# SCH_uCompute_NRF24L01_module_2026-04-06.net
KiCad netlist of a schematic drawn in EasyEDA
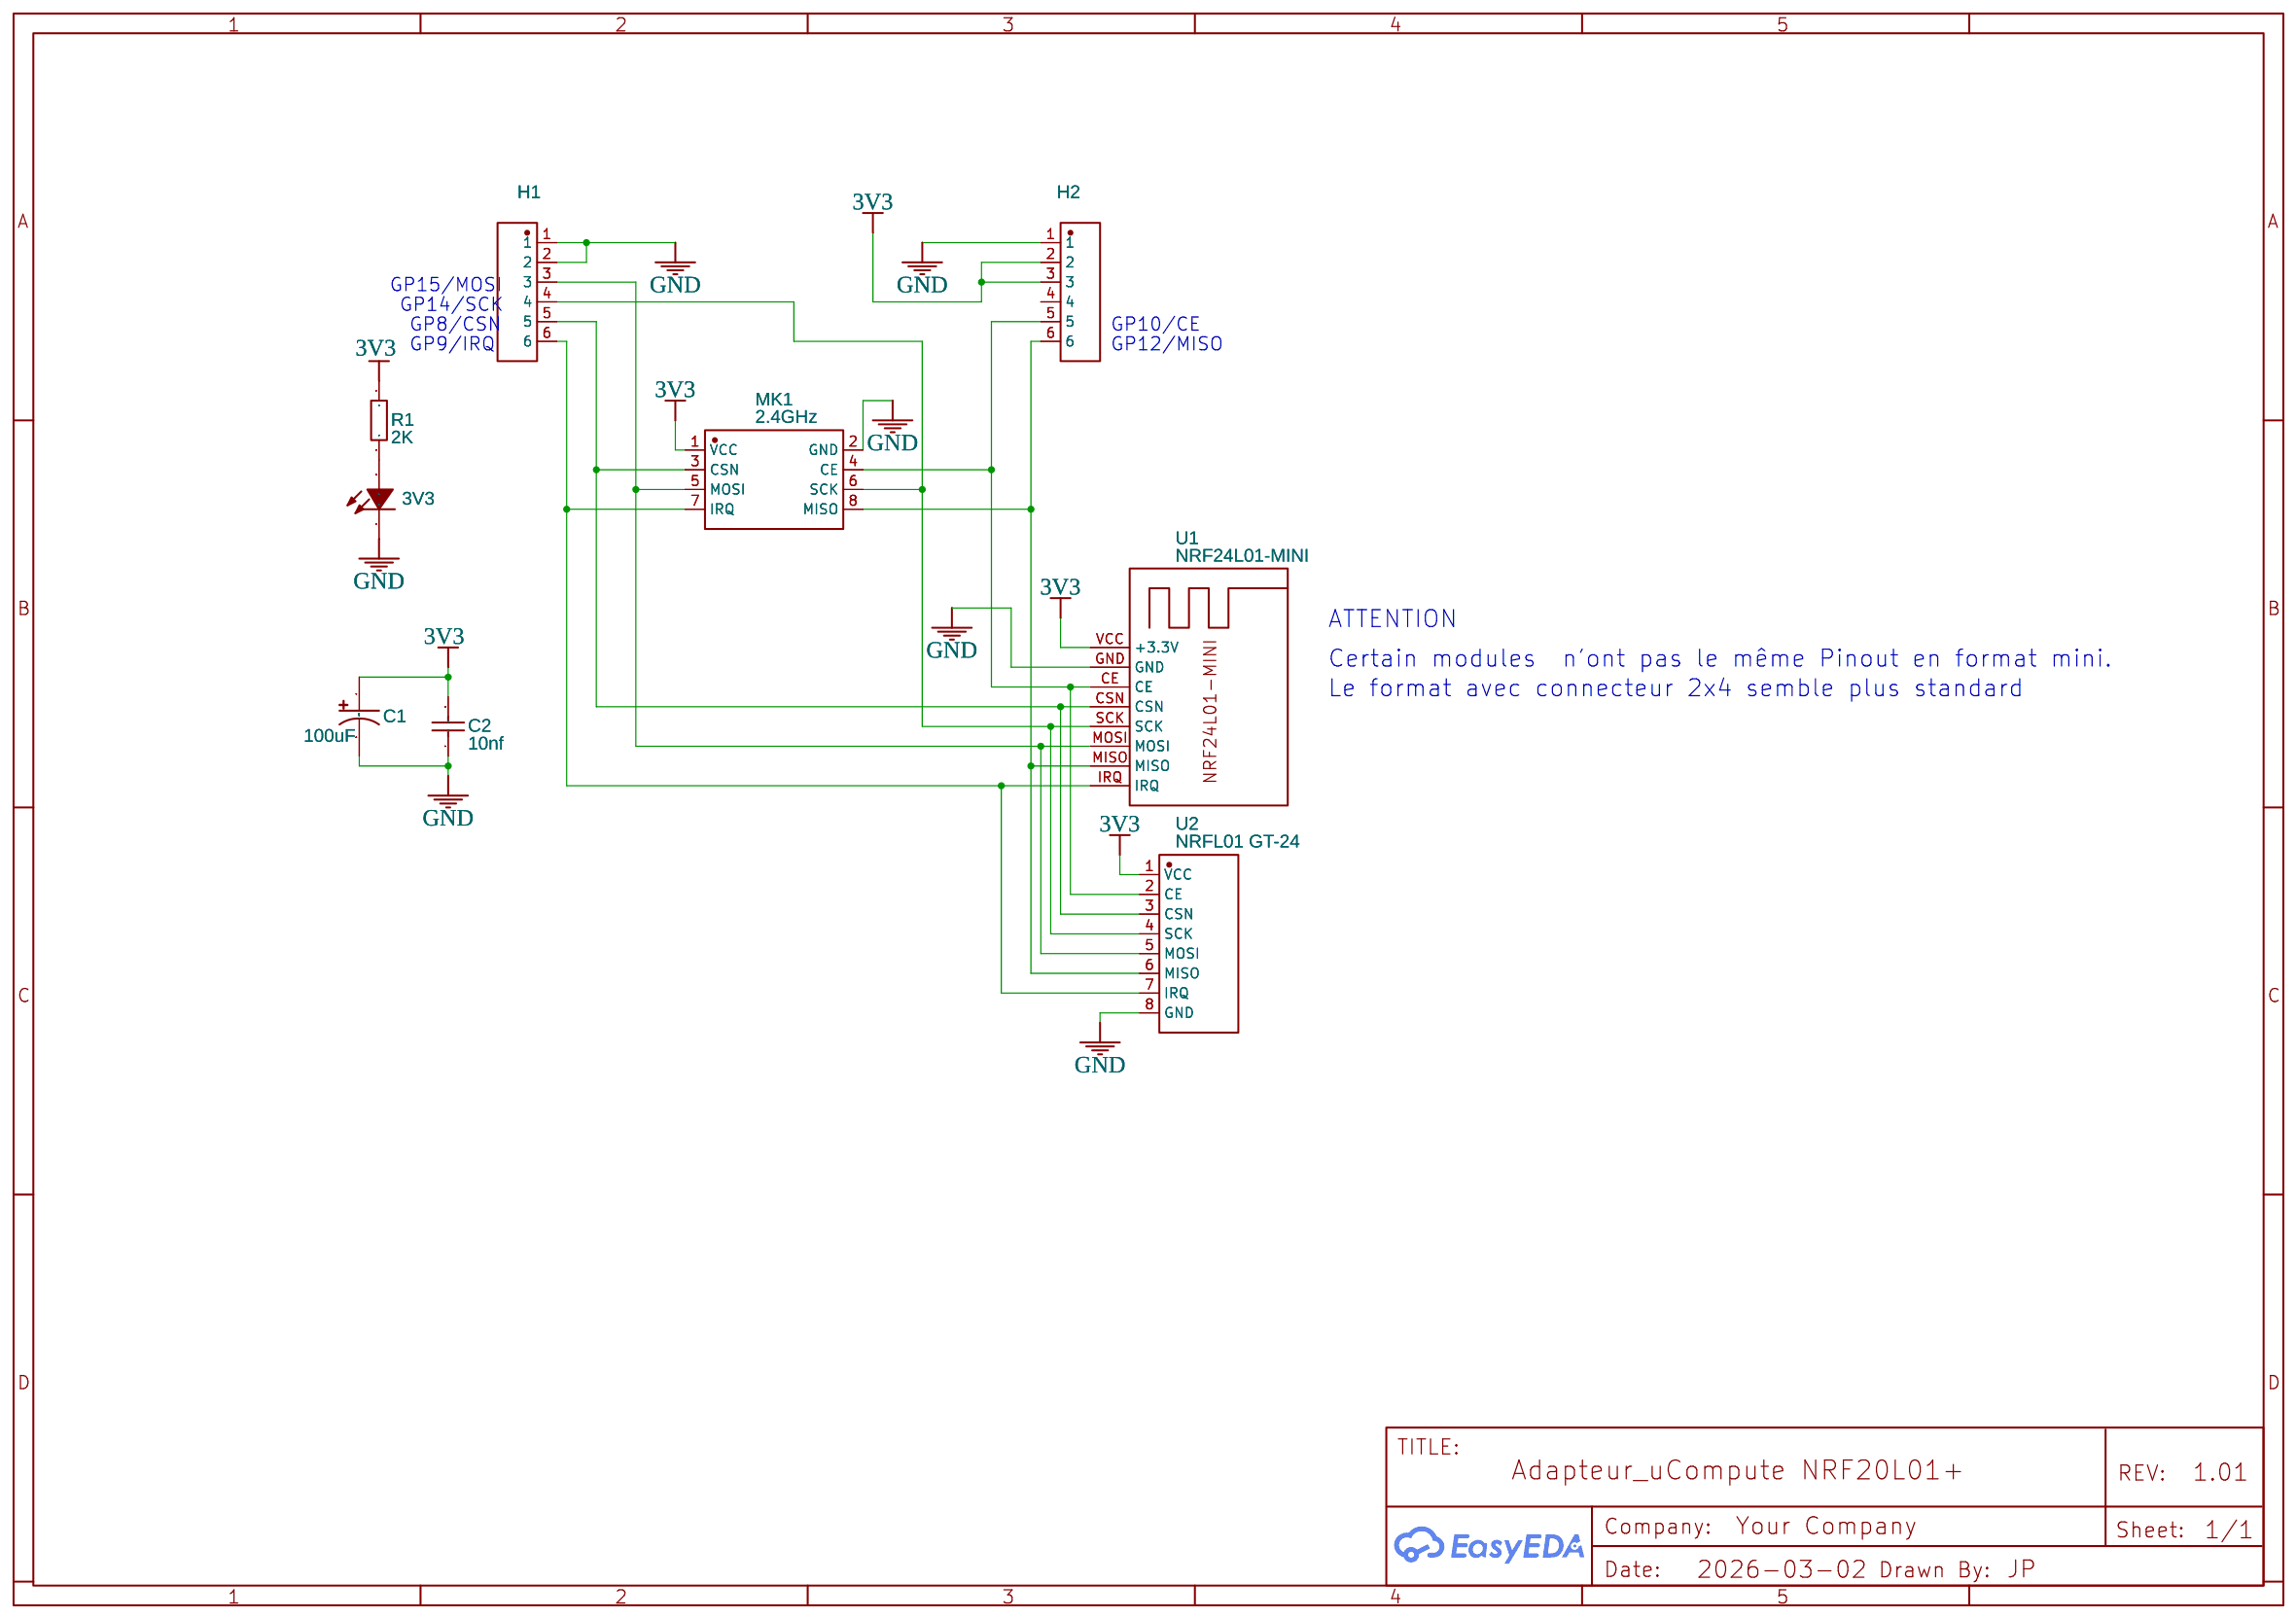
[diagram p0: schematic sheet]

(export (version "E")
  (design (tool "Eeschema 10.0.6"))
  (components
    (comp (ref "3V3")
      (value "XL-1206QPC")
      (fields (field (name "Manufacturer") "LCSC"))
      (libsource (lib "") (part "XL-1206QPC"))
    )
    (comp (ref "C1")
      (value "100uF")
      (fields
        (field (name "Manufacturer Part") "TLJA107M010R1400")
        (field (name "Manufacturer") "Kyocera AVX")
      )
      (libsource (lib "") (part "TLJA107M010R1400"))
    )
    (comp (ref "C2")
      (value "10nf")
      (fields (field (name "Manufacturer Part") "0805CG220J500NT") (field (name "Manufacturer") "FH"))
      (libsource (lib "") (part "0805CG220J500NT"))
    )
    (comp (ref "H1")
      (value "KH-2.54PH180-1X6P-L11.5")
      (fields (field (name "Manufacturer") "kinghelm(金航标)"))
      (libsource (lib "") (part "KH-2.54PH180-1X6P-L11.5"))
    )
    (comp (ref "H2")
      (value "KH-2.54PH180-1X6P-L11.5")
      (fields (field (name "Manufacturer") "kinghelm(金航标)"))
      (libsource (lib "") (part "KH-2.54PH180-1X6P-L11.5_1"))
    )
    (comp (ref "MK1")
      (value "2.4GHz")
      (fields (field (name "Manufacturer Part") "NF-04") (field (name "Manufacturer") "Ai-Thinker(安信可)"))
      (libsource (lib "") (part "NRF24L01"))
    )
    (comp (ref "R1")
      (value "2K")
      (fields (field (name "Manufacturer Part") "RC0805DR-071KL") (field (name "Manufacturer") "YAGEO(国巨)"))
      (libsource (lib "") (part "RC0805DR-071KL"))
    )
    (comp (ref "U1") (value "NRF24L01-MINI") (libsource (lib "") (part "NRF24L01-MINI")))
    (comp (ref "U2") (value "NRFL01 GT-24") (libsource (lib "") (part "NRFL01 GT-24")))
  )
  (nets
    (net (code "1") (name "3V3") (class "Default")
      (node (ref "C1") (pin "1") (pinfunction "1_1") (pintype "unspecified"))
      (node (ref "C2") (pin "2") (pinfunction "2_2") (pintype "input"))
      (node (ref "H2") (pin "2") (pinfunction "2_2") (pintype "unspecified"))
      (node (ref "H2") (pin "3") (pinfunction "3_3") (pintype "unspecified"))
      (node (ref "MK1") (pin "1") (pinfunction "VCC_1") (pintype "unspecified"))
      (node (ref "R1") (pin "1") (pinfunction "1_1") (pintype "unspecified"))
      (node (ref "U1") (pin "VCC") (pinfunction "+3.3V_VCC") (pintype "passive"))
      (node (ref "U2") (pin "1") (pinfunction "VCC_1") (pintype "unspecified"))
    )
    (net (code "2") (name "GND") (class "Default")
      (node (ref "3V3") (pin "1") (pinfunction "K_1") (pintype "unspecified"))
      (node (ref "C1") (pin "2") (pinfunction "2_2") (pintype "unspecified"))
      (node (ref "C2") (pin "1") (pinfunction "1_1") (pintype "input"))
      (node (ref "H1") (pin "1") (pinfunction "1_1") (pintype "unspecified"))
      (node (ref "H1") (pin "2") (pinfunction "2_2") (pintype "unspecified"))
      (node (ref "H2") (pin "1") (pinfunction "1_1") (pintype "unspecified"))
      (node (ref "MK1") (pin "2") (pinfunction "GND_2") (pintype "unspecified"))
      (node (ref "U1") (pin "GND") (pinfunction "GND_GND") (pintype "unspecified"))
      (node (ref "U2") (pin "8") (pinfunction "GND_8") (pintype "unspecified"))
    )
    (net (code "3") (name "Net-(3V3-A)") (class "Default")
      (node (ref "3V3") (pin "2") (pinfunction "A_2") (pintype "unspecified"))
      (node (ref "R1") (pin "2") (pinfunction "2_2") (pintype "unspecified"))
    )
    (net (code "4") (name "Net-(MK1-CE)") (class "Default")
      (node (ref "H2") (pin "5") (pinfunction "5_5") (pintype "unspecified"))
      (node (ref "MK1") (pin "4") (pinfunction "CE_4") (pintype "unspecified"))
      (node (ref "U1") (pin "CE") (pinfunction "CE_CE") (pintype "bidirectional"))
      (node (ref "U2") (pin "2") (pinfunction "CE_2") (pintype "unspecified"))
    )
    (net (code "5") (name "Net-(MK1-CSN)") (class "Default")
      (node (ref "H1") (pin "5") (pinfunction "5_5") (pintype "unspecified"))
      (node (ref "MK1") (pin "3") (pinfunction "CSN_3") (pintype "unspecified"))
      (node (ref "U1") (pin "CSN") (pinfunction "CSN_CSN") (pintype "bidirectional"))
      (node (ref "U2") (pin "3") (pinfunction "CSN_3") (pintype "unspecified"))
    )
    (net (code "6") (name "Net-(MK1-IRQ)") (class "Default")
      (node (ref "H1") (pin "6") (pinfunction "6_6") (pintype "unspecified"))
      (node (ref "MK1") (pin "7") (pinfunction "IRQ_7") (pintype "unspecified"))
      (node (ref "U1") (pin "IRQ") (pinfunction "IRQ_IRQ") (pintype "unspecified"))
      (node (ref "U2") (pin "7") (pinfunction "IRQ_7") (pintype "unspecified"))
    )
    (net (code "7") (name "Net-(MK1-MISO)") (class "Default")
      (node (ref "H2") (pin "6") (pinfunction "6_6") (pintype "unspecified"))
      (node (ref "MK1") (pin "8") (pinfunction "MISO_8") (pintype "unspecified"))
      (node (ref "U1") (pin "MISO") (pinfunction "MISO_MISO") (pintype "output"))
      (node (ref "U2") (pin "6") (pinfunction "MISO_6") (pintype "unspecified"))
    )
    (net (code "8") (name "Net-(MK1-MOSI)") (class "Default")
      (node (ref "H1") (pin "3") (pinfunction "3_3") (pintype "unspecified"))
      (node (ref "MK1") (pin "5") (pinfunction "MOSI_5") (pintype "unspecified"))
      (node (ref "U1") (pin "MOSI") (pinfunction "MOSI_MOSI") (pintype "bidirectional"))
      (node (ref "U2") (pin "5") (pinfunction "MOSI_5") (pintype "unspecified"))
    )
    (net (code "9") (name "Net-(MK1-SCK)") (class "Default")
      (node (ref "H1") (pin "4") (pinfunction "4_4") (pintype "unspecified"))
      (node (ref "MK1") (pin "6") (pinfunction "SCK_6") (pintype "unspecified"))
      (node (ref "U1") (pin "SCK") (pinfunction "SCK_SCK") (pintype "bidirectional"))
      (node (ref "U2") (pin "4") (pinfunction "SCK_4") (pintype "unspecified"))
    )
    (net (code "10") (name "unconnected-(H2-Pad4)") (class "Default")
      (node (ref "H2") (pin "4") (pinfunction "4_4") (pintype "unspecified"))
    )
  )
)
